# stm32-motor-driver.net
KiCad netlist of a schematic drawn in Altium Designer
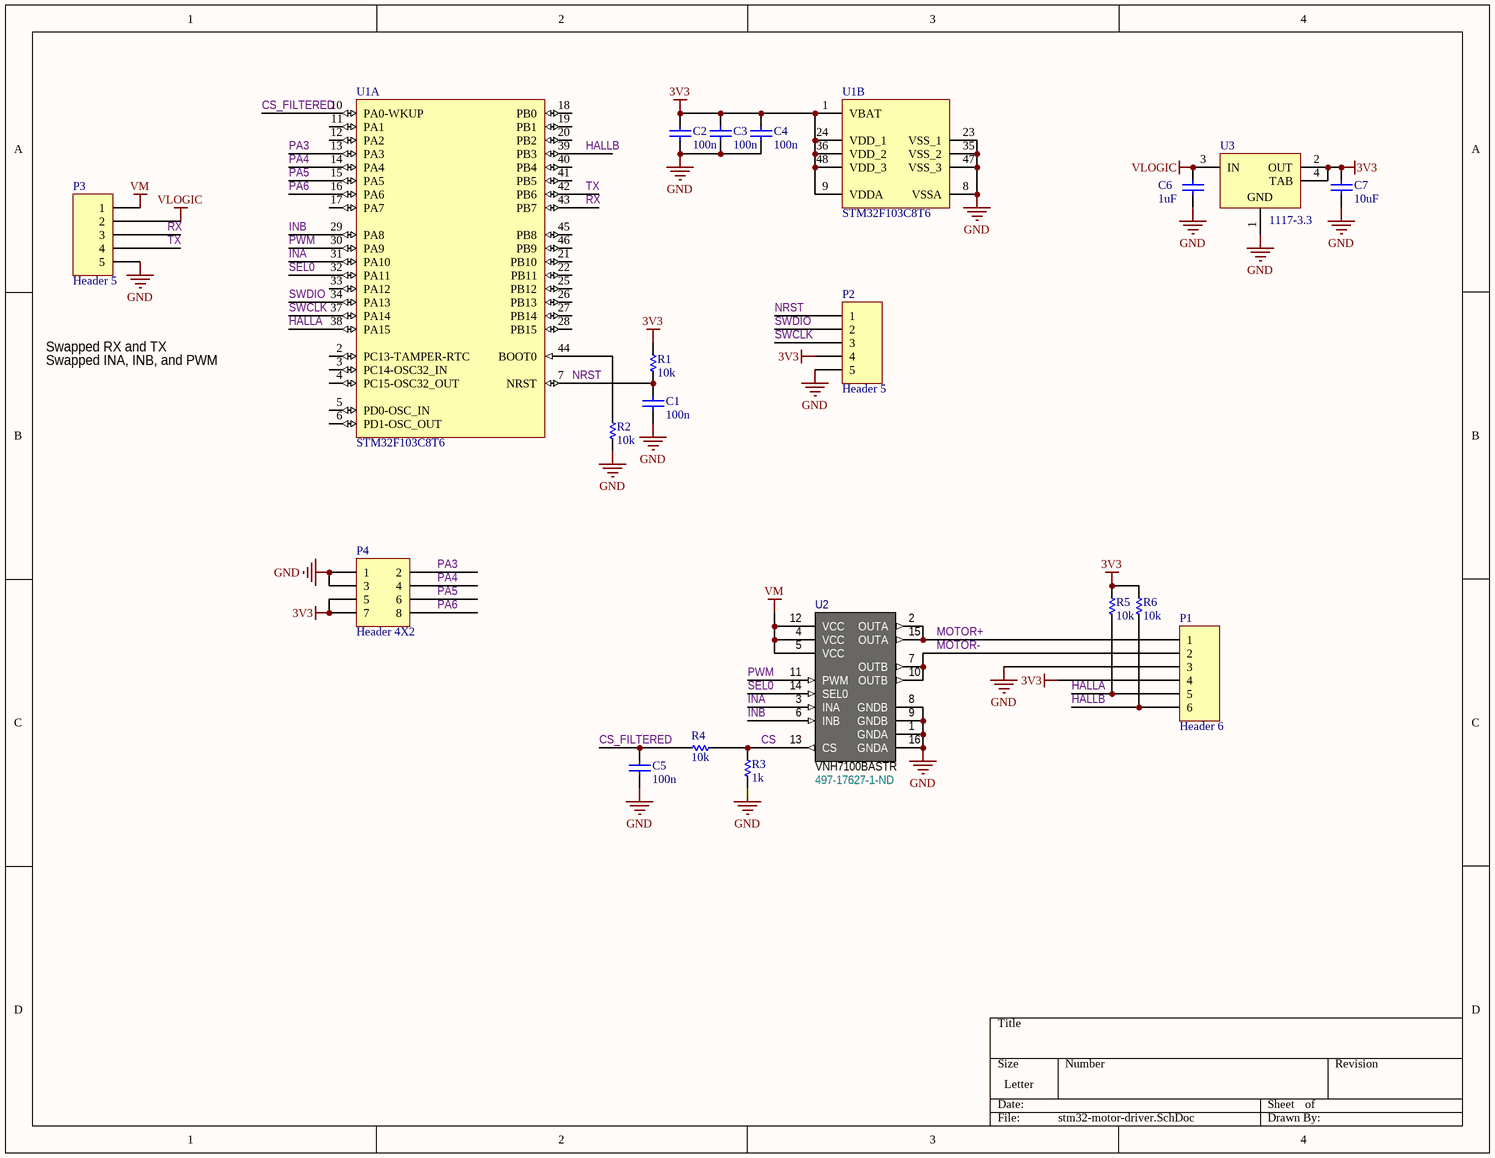
[diagram p0: stm32-motor-driver.SchDoc]

(export (version "E")
  (design (tool "Eeschema 10.0.6"))
  (components
    (comp (ref "C1")
      (value "100n")
      (footprint "CAPC1608N")
      (description "Capacitor")
      (fields (field (name "TOLERANCE") "%") (field (name "Comment") "100n CAPC1608N"))
      (libsource (lib "Miscellaneous Devices") (part "Cap Chip"))
    )
    (comp (ref "C2")
      (value "100n")
      (footprint "CAPC1608N")
      (description "Capacitor")
      (fields (field (name "TOLERANCE") "%") (field (name "Comment") "100n CAPC1608N"))
      (libsource (lib "Miscellaneous Devices") (part "Cap Chip"))
    )
    (comp (ref "C3")
      (value "100n")
      (footprint "CAPC1608N")
      (description "Capacitor")
      (fields (field (name "TOLERANCE") "%") (field (name "Comment") "100n CAPC1608N"))
      (libsource (lib "Miscellaneous Devices") (part "Cap Chip"))
    )
    (comp (ref "C4")
      (value "100n")
      (footprint "CAPC1608N")
      (description "Capacitor")
      (fields (field (name "TOLERANCE") "%") (field (name "Comment") "100n CAPC1608N"))
      (libsource (lib "Miscellaneous Devices") (part "Cap Chip"))
    )
    (comp (ref "C5")
      (value "100n")
      (footprint "CAPC1608N")
      (description "Capacitor")
      (fields (field (name "TOLERANCE") "%") (field (name "Comment") "100n CAPC1608N"))
      (libsource (lib "Miscellaneous Devices") (part "Cap Chip"))
    )
    (comp (ref "C6")
      (value "1uF")
      (footprint "CAPC1608N")
      (description "Capacitor")
      (fields (field (name "TOLERANCE") "%") (field (name "Comment") "1uF CAPC1608N"))
      (libsource (lib "Miscellaneous Devices") (part "Cap Chip"))
    )
    (comp (ref "C7")
      (value "10uF")
      (footprint "CAPC1608N")
      (description "Capacitor")
      (fields (field (name "TOLERANCE") "%") (field (name "Comment") "10uF CAPC1608N"))
      (libsource (lib "Miscellaneous Devices") (part "Cap Chip"))
    )
    (comp (ref "P1")
      (value "Header 6")
      (footprint "HDR1X6-PINS")
      (description "Header, 6-Pin")
      (fields (field (name "PUBLISHER") "Altium Limited"))
      (libsource (lib "Miscellaneous Connectors") (part "Header 6"))
    )
    (comp (ref "P2")
      (value "Header 5")
      (footprint "HDR1X5")
      (description "Header, 5-Pin")
      (fields (field (name "PUBLISHER") "Altium Limited"))
      (libsource (lib "Miscellaneous Connectors") (part "Header 5"))
    )
    (comp (ref "P3")
      (value "Header 5")
      (footprint "HDR1X5")
      (description "Header, 5-Pin")
      (fields (field (name "PUBLISHER") "Altium Limited"))
      (libsource (lib "") (part "Header 5_1"))
    )
    (comp (ref "P4")
      (value "Header 4X2")
      (footprint "HDR2X4")
      (description "Header, 4-Pin, Dual row")
      (fields (field (name "PUBLISHER") "Altium Limited"))
      (libsource (lib "Miscellaneous Connectors") (part "Header 4X2"))
    )
    (comp (ref "R1")
      (value "10k")
      (footprint "RESC1608N")
      (description "Chip Resistor")
      (fields (field (name "TOLERANCE") "%") (field (name "Comment") "10k RESC1608N"))
      (libsource (lib "Miscellaneous Devices") (part "Res Chip"))
    )
    (comp (ref "R2")
      (value "10k")
      (footprint "RESC1608N")
      (description "Chip Resistor")
      (fields (field (name "TOLERANCE") "%") (field (name "Comment") "10k RESC1608N"))
      (libsource (lib "Miscellaneous Devices") (part "Res Chip"))
    )
    (comp (ref "R3")
      (value "1k")
      (footprint "RESC1608N")
      (description "Chip Resistor")
      (fields (field (name "TOLERANCE") "%") (field (name "Comment") "1k RESC1608N"))
      (libsource (lib "Miscellaneous Devices") (part "Res Chip"))
    )
    (comp (ref "R4")
      (value "10k")
      (footprint "RESC1608N")
      (description "Chip Resistor")
      (fields (field (name "TOLERANCE") "%") (field (name "Comment") "10k RESC1608N"))
      (libsource (lib "Miscellaneous Devices") (part "Res Chip"))
    )
    (comp (ref "R5")
      (value "10k")
      (footprint "RESC1608N")
      (description "Chip Resistor")
      (fields (field (name "TOLERANCE") "%") (field (name "Comment") "10k RESC1608N"))
      (libsource (lib "Miscellaneous Devices") (part "Res Chip"))
    )
    (comp (ref "R6")
      (value "10k")
      (footprint "RESC1608N")
      (description "Chip Resistor")
      (fields (field (name "TOLERANCE") "%") (field (name "Comment") "10k RESC1608N"))
      (libsource (lib "Miscellaneous Devices") (part "Res Chip"))
    )
    (comp (ref "U1")
      (value "STM32F103C8T6")
      (footprint "STM-LQFP48_L")
      (libsource (lib "Altium Content Vault") (part "MC-ARM-STM32F103X8_B-SQ48"))
    )
    (comp (ref "U2")
      (value "VNH7100BASTR")
      (footprint "SOIC127P600-16N")
      (description "SO 16 .15 TO JEDEC MS-012")
      (fields
        (field (name "MANUFACTURER") "STMicroelectronics")
        (field (name "SUPPLIER PART NUMBER 1") "497-17627-1-ND")
      )
      (libsource (lib "ST Motor Driver") (part "VNH7100BASTR"))
    )
    (comp (ref "U3")
      (value "1117-3.3")
      (footprint "DCY0004A_N")
      (description "800mA Low-Dropout Linear Regulator, 4-pin SOT-223, Pb-Free")
      (fields
        (field (name "PARTNUMBER") "LM1117IMP-3.3/NOPB")
        (field (name "MANUFACTURER") "Texas Instruments")
      )
      (libsource (lib "Altium Content Vault") (part "PM-REG-LM1086-SOT4"))
    )
  )
  (nets
    (net (code "1") (name "/CS") (class "Default")
      (node (ref "R3") (pin "2") (pinfunction "2_2") (pintype "passive"))
      (node (ref "R4") (pin "1") (pinfunction "1_1") (pintype "passive"))
      (node (ref "U2") (pin "13") (pinfunction "CS_13") (pintype "output"))
    )
    (net (code "2") (name "/CS_FILTERED") (class "Default")
      (node (ref "C5") (pin "2") (pinfunction "2_2") (pintype "passive"))
      (node (ref "R4") (pin "2") (pinfunction "2_2") (pintype "passive"))
      (node (ref "U1") (pin "10") (pinfunction "PA0-WKUP_10") (pintype "bidirectional"))
    )
    (net (code "3") (name "/HALLA") (class "Default")
      (node (ref "P1") (pin "5") (pinfunction "5_5") (pintype "passive"))
      (node (ref "R5") (pin "1") (pinfunction "1_1") (pintype "passive"))
      (node (ref "U1") (pin "38") (pinfunction "PA15_38") (pintype "bidirectional"))
    )
    (net (code "4") (name "/HALLB") (class "Default")
      (node (ref "P1") (pin "6") (pinfunction "6_6") (pintype "passive"))
      (node (ref "R6") (pin "1") (pinfunction "1_1") (pintype "passive"))
      (node (ref "U1") (pin "39") (pinfunction "PB3_39") (pintype "bidirectional"))
    )
    (net (code "5") (name "/INA") (class "Default")
      (node (ref "U1") (pin "31") (pinfunction "PA10_31") (pintype "bidirectional"))
      (node (ref "U2") (pin "3") (pinfunction "INA_3") (pintype "input"))
    )
    (net (code "6") (name "/INB") (class "Default")
      (node (ref "U1") (pin "29") (pinfunction "PA8_29") (pintype "bidirectional"))
      (node (ref "U2") (pin "6") (pinfunction "INB_6") (pintype "input"))
    )
    (net (code "7") (name "/MOTOR+") (class "Default")
      (node (ref "P1") (pin "1") (pinfunction "1_1") (pintype "passive"))
      (node (ref "U2") (pin "15") (pinfunction "OUTA_15") (pintype "output"))
      (node (ref "U2") (pin "2") (pinfunction "OUTA_2") (pintype "output"))
    )
    (net (code "8") (name "/MOTOR-") (class "Default")
      (node (ref "P1") (pin "2") (pinfunction "2_2") (pintype "passive"))
      (node (ref "U2") (pin "10") (pinfunction "OUTB_10") (pintype "output"))
      (node (ref "U2") (pin "7") (pinfunction "OUTB_7") (pintype "output"))
    )
    (net (code "9") (name "/NRST") (class "Default")
      (node (ref "C1") (pin "2") (pinfunction "2_2") (pintype "passive"))
      (node (ref "P2") (pin "1") (pinfunction "1_1") (pintype "passive"))
      (node (ref "R1") (pin "1") (pinfunction "1_1") (pintype "passive"))
      (node (ref "U1") (pin "7") (pinfunction "NRST_7") (pintype "bidirectional"))
    )
    (net (code "10") (name "/PA3") (class "Default")
      (node (ref "P4") (pin "2") (pinfunction "2_2") (pintype "passive"))
      (node (ref "U1") (pin "13") (pinfunction "PA3_13") (pintype "bidirectional"))
    )
    (net (code "11") (name "/PA4") (class "Default")
      (node (ref "P4") (pin "4") (pinfunction "4_4") (pintype "passive"))
      (node (ref "U1") (pin "14") (pinfunction "PA4_14") (pintype "bidirectional"))
    )
    (net (code "12") (name "/PA5") (class "Default")
      (node (ref "P4") (pin "6") (pinfunction "6_6") (pintype "passive"))
      (node (ref "U1") (pin "15") (pinfunction "PA5_15") (pintype "bidirectional"))
    )
    (net (code "13") (name "/PA6") (class "Default")
      (node (ref "P4") (pin "8") (pinfunction "8_8") (pintype "passive"))
      (node (ref "U1") (pin "16") (pinfunction "PA6_16") (pintype "bidirectional"))
    )
    (net (code "14") (name "/PWM") (class "Default")
      (node (ref "U1") (pin "30") (pinfunction "PA9_30") (pintype "bidirectional"))
      (node (ref "U2") (pin "11") (pinfunction "PWM_11") (pintype "input"))
    )
    (net (code "15") (name "/RX") (class "Default")
      (node (ref "P3") (pin "3") (pinfunction "3_3") (pintype "passive"))
      (node (ref "U1") (pin "43") (pinfunction "PB7_43") (pintype "bidirectional"))
    )
    (net (code "16") (name "/SEL0") (class "Default")
      (node (ref "U1") (pin "32") (pinfunction "PA11_32") (pintype "bidirectional"))
      (node (ref "U2") (pin "14") (pinfunction "SEL0_14") (pintype "input"))
    )
    (net (code "17") (name "/SWCLK") (class "Default")
      (node (ref "P2") (pin "3") (pinfunction "3_3") (pintype "passive"))
      (node (ref "U1") (pin "37") (pinfunction "PA14_37") (pintype "bidirectional"))
    )
    (net (code "18") (name "/SWDIO") (class "Default")
      (node (ref "P2") (pin "2") (pinfunction "2_2") (pintype "passive"))
      (node (ref "U1") (pin "34") (pinfunction "PA13_34") (pintype "bidirectional"))
    )
    (net (code "19") (name "/TX") (class "Default")
      (node (ref "P3") (pin "4") (pinfunction "4_4") (pintype "passive"))
      (node (ref "U1") (pin "42") (pinfunction "PB6_42") (pintype "bidirectional"))
    )
    (net (code "20") (name "3V3") (class "Default")
      (node (ref "C2") (pin "2") (pinfunction "2_2") (pintype "passive"))
      (node (ref "C3") (pin "2") (pinfunction "2_2") (pintype "passive"))
      (node (ref "C4") (pin "2") (pinfunction "2_2") (pintype "passive"))
      (node (ref "C7") (pin "2") (pinfunction "2_2") (pintype "passive"))
      (node (ref "P1") (pin "4") (pinfunction "4_4") (pintype "passive"))
      (node (ref "P2") (pin "4") (pinfunction "4_4") (pintype "passive"))
      (node (ref "P4") (pin "5") (pinfunction "5_5") (pintype "passive"))
      (node (ref "P4") (pin "7") (pinfunction "7_7") (pintype "passive"))
      (node (ref "R1") (pin "2") (pinfunction "2_2") (pintype "passive"))
      (node (ref "R5") (pin "2") (pinfunction "2_2") (pintype "passive"))
      (node (ref "R6") (pin "2") (pinfunction "2_2") (pintype "passive"))
      (node (ref "U1") (pin "1") (pinfunction "VBAT_1") (pintype "power_in"))
      (node (ref "U1") (pin "24") (pinfunction "VDD_1_24") (pintype "power_in"))
      (node (ref "U1") (pin "36") (pinfunction "VDD_2_36") (pintype "power_in"))
      (node (ref "U1") (pin "48") (pinfunction "VDD_3_48") (pintype "power_in"))
      (node (ref "U1") (pin "9") (pinfunction "VDDA_9") (pintype "power_in"))
      (node (ref "U3") (pin "2") (pinfunction "OUT_2") (pintype "power_in"))
      (node (ref "U3") (pin "4") (pinfunction "TAB_4") (pintype "power_in"))
    )
    (net (code "21") (name "GND") (class "Default")
      (node (ref "C1") (pin "1") (pinfunction "1_1") (pintype "passive"))
      (node (ref "C2") (pin "1") (pinfunction "1_1") (pintype "passive"))
      (node (ref "C3") (pin "1") (pinfunction "1_1") (pintype "passive"))
      (node (ref "C4") (pin "1") (pinfunction "1_1") (pintype "passive"))
      (node (ref "C5") (pin "1") (pinfunction "1_1") (pintype "passive"))
      (node (ref "C6") (pin "1") (pinfunction "1_1") (pintype "passive"))
      (node (ref "C7") (pin "1") (pinfunction "1_1") (pintype "passive"))
      (node (ref "P1") (pin "3") (pinfunction "3_3") (pintype "passive"))
      (node (ref "P2") (pin "5") (pinfunction "5_5") (pintype "passive"))
      (node (ref "P3") (pin "5") (pinfunction "5_5") (pintype "passive"))
      (node (ref "P4") (pin "1") (pinfunction "1_1") (pintype "passive"))
      (node (ref "P4") (pin "3") (pinfunction "3_3") (pintype "passive"))
      (node (ref "R2") (pin "1") (pinfunction "1_1") (pintype "passive"))
      (node (ref "R3") (pin "1") (pinfunction "1_1") (pintype "passive"))
      (node (ref "U1") (pin "23") (pinfunction "VSS_1_23") (pintype "power_in"))
      (node (ref "U1") (pin "35") (pinfunction "VSS_2_35") (pintype "power_in"))
      (node (ref "U1") (pin "47") (pinfunction "VSS_3_47") (pintype "power_in"))
      (node (ref "U1") (pin "8") (pinfunction "VSSA_8") (pintype "power_in"))
      (node (ref "U2") (pin "1") (pinfunction "GNDA_1") (pintype "power_in"))
      (node (ref "U2") (pin "16") (pinfunction "GNDA_16") (pintype "power_in"))
      (node (ref "U2") (pin "8") (pinfunction "GNDB_8") (pintype "power_in"))
      (node (ref "U2") (pin "9") (pinfunction "GNDB_9") (pintype "power_in"))
      (node (ref "U3") (pin "1") (pinfunction "GND_1") (pintype "power_in"))
    )
    (net (code "22") (name "Net-(U1A-BOOT0)") (class "Default")
      (node (ref "R2") (pin "2") (pinfunction "2_2") (pintype "passive"))
      (node (ref "U1") (pin "44") (pinfunction "BOOT0_44") (pintype "input"))
    )
    (net (code "23") (name "VLOGIC") (class "Default")
      (node (ref "C6") (pin "2") (pinfunction "2_2") (pintype "passive"))
      (node (ref "P3") (pin "2") (pinfunction "2_2") (pintype "passive"))
      (node (ref "U3") (pin "3") (pinfunction "IN_3") (pintype "power_in"))
    )
    (net (code "24") (name "VM") (class "Default")
      (node (ref "P3") (pin "1") (pinfunction "1_1") (pintype "passive"))
      (node (ref "U2") (pin "12") (pinfunction "VCC_12") (pintype "power_in"))
      (node (ref "U2") (pin "4") (pinfunction "VCC_4") (pintype "power_in"))
      (node (ref "U2") (pin "5") (pinfunction "VCC_5") (pintype "power_in"))
    )
    (net (code "25") (name "unconnected-(U1A-PA1-Pad11)") (class "Default")
      (node (ref "U1") (pin "11") (pinfunction "PA1_11") (pintype "bidirectional"))
    )
    (net (code "26") (name "unconnected-(U1A-PA2-Pad12)") (class "Default")
      (node (ref "U1") (pin "12") (pinfunction "PA2_12") (pintype "bidirectional"))
    )
    (net (code "27") (name "unconnected-(U1A-PA7-Pad17)") (class "Default")
      (node (ref "U1") (pin "17") (pinfunction "PA7_17") (pintype "bidirectional"))
    )
    (net (code "28") (name "unconnected-(U1A-PA12-Pad33)") (class "Default")
      (node (ref "U1") (pin "33") (pinfunction "PA12_33") (pintype "bidirectional"))
    )
    (net (code "29") (name "unconnected-(U1A-PB0-Pad18)") (class "Default")
      (node (ref "U1") (pin "18") (pinfunction "PB0_18") (pintype "bidirectional"))
    )
    (net (code "30") (name "unconnected-(U1A-PB1-Pad19)") (class "Default")
      (node (ref "U1") (pin "19") (pinfunction "PB1_19") (pintype "bidirectional"))
    )
    (net (code "31") (name "unconnected-(U1A-PB2-Pad20)") (class "Default")
      (node (ref "U1") (pin "20") (pinfunction "PB2_20") (pintype "bidirectional"))
    )
    (net (code "32") (name "unconnected-(U1A-PB4-Pad40)") (class "Default")
      (node (ref "U1") (pin "40") (pinfunction "PB4_40") (pintype "bidirectional"))
    )
    (net (code "33") (name "unconnected-(U1A-PB5-Pad41)") (class "Default")
      (node (ref "U1") (pin "41") (pinfunction "PB5_41") (pintype "bidirectional"))
    )
    (net (code "34") (name "unconnected-(U1A-PB8-Pad45)") (class "Default")
      (node (ref "U1") (pin "45") (pinfunction "PB8_45") (pintype "bidirectional"))
    )
    (net (code "35") (name "unconnected-(U1A-PB9-Pad46)") (class "Default")
      (node (ref "U1") (pin "46") (pinfunction "PB9_46") (pintype "bidirectional"))
    )
    (net (code "36") (name "unconnected-(U1A-PB10-Pad21)") (class "Default")
      (node (ref "U1") (pin "21") (pinfunction "PB10_21") (pintype "bidirectional"))
    )
    (net (code "37") (name "unconnected-(U1A-PB11-Pad22)") (class "Default")
      (node (ref "U1") (pin "22") (pinfunction "PB11_22") (pintype "bidirectional"))
    )
    (net (code "38") (name "unconnected-(U1A-PB12-Pad25)") (class "Default")
      (node (ref "U1") (pin "25") (pinfunction "PB12_25") (pintype "bidirectional"))
    )
    (net (code "39") (name "unconnected-(U1A-PB13-Pad26)") (class "Default")
      (node (ref "U1") (pin "26") (pinfunction "PB13_26") (pintype "bidirectional"))
    )
    (net (code "40") (name "unconnected-(U1A-PB14-Pad27)") (class "Default")
      (node (ref "U1") (pin "27") (pinfunction "PB14_27") (pintype "bidirectional"))
    )
    (net (code "41") (name "unconnected-(U1A-PB15-Pad28)") (class "Default")
      (node (ref "U1") (pin "28") (pinfunction "PB15_28") (pintype "bidirectional"))
    )
    (net (code "42") (name "unconnected-(U1A-PC13-TAMPER-RTC-Pad2)") (class "Default")
      (node (ref "U1") (pin "2") (pinfunction "PC13-TAMPER-RTC_2") (pintype "bidirectional"))
    )
    (net (code "43") (name "unconnected-(U1A-PC14-OSC32_IN-Pad3)") (class "Default")
      (node (ref "U1") (pin "3") (pinfunction "PC14-OSC32_IN_3") (pintype "bidirectional"))
    )
    (net (code "44") (name "unconnected-(U1A-PC15-OSC32_OUT-Pad4)") (class "Default")
      (node (ref "U1") (pin "4") (pinfunction "PC15-OSC32_OUT_4") (pintype "bidirectional"))
    )
    (net (code "45") (name "unconnected-(U1A-PD0-OSC_IN-Pad5)") (class "Default")
      (node (ref "U1") (pin "5") (pinfunction "PD0-OSC_IN_5") (pintype "bidirectional"))
    )
    (net (code "46") (name "unconnected-(U1A-PD1-OSC_OUT-Pad6)") (class "Default")
      (node (ref "U1") (pin "6") (pinfunction "PD1-OSC_OUT_6") (pintype "bidirectional"))
    )
  )
)
